# cutoff.net
KiCad netlist of a schematic drawn in EAGLE
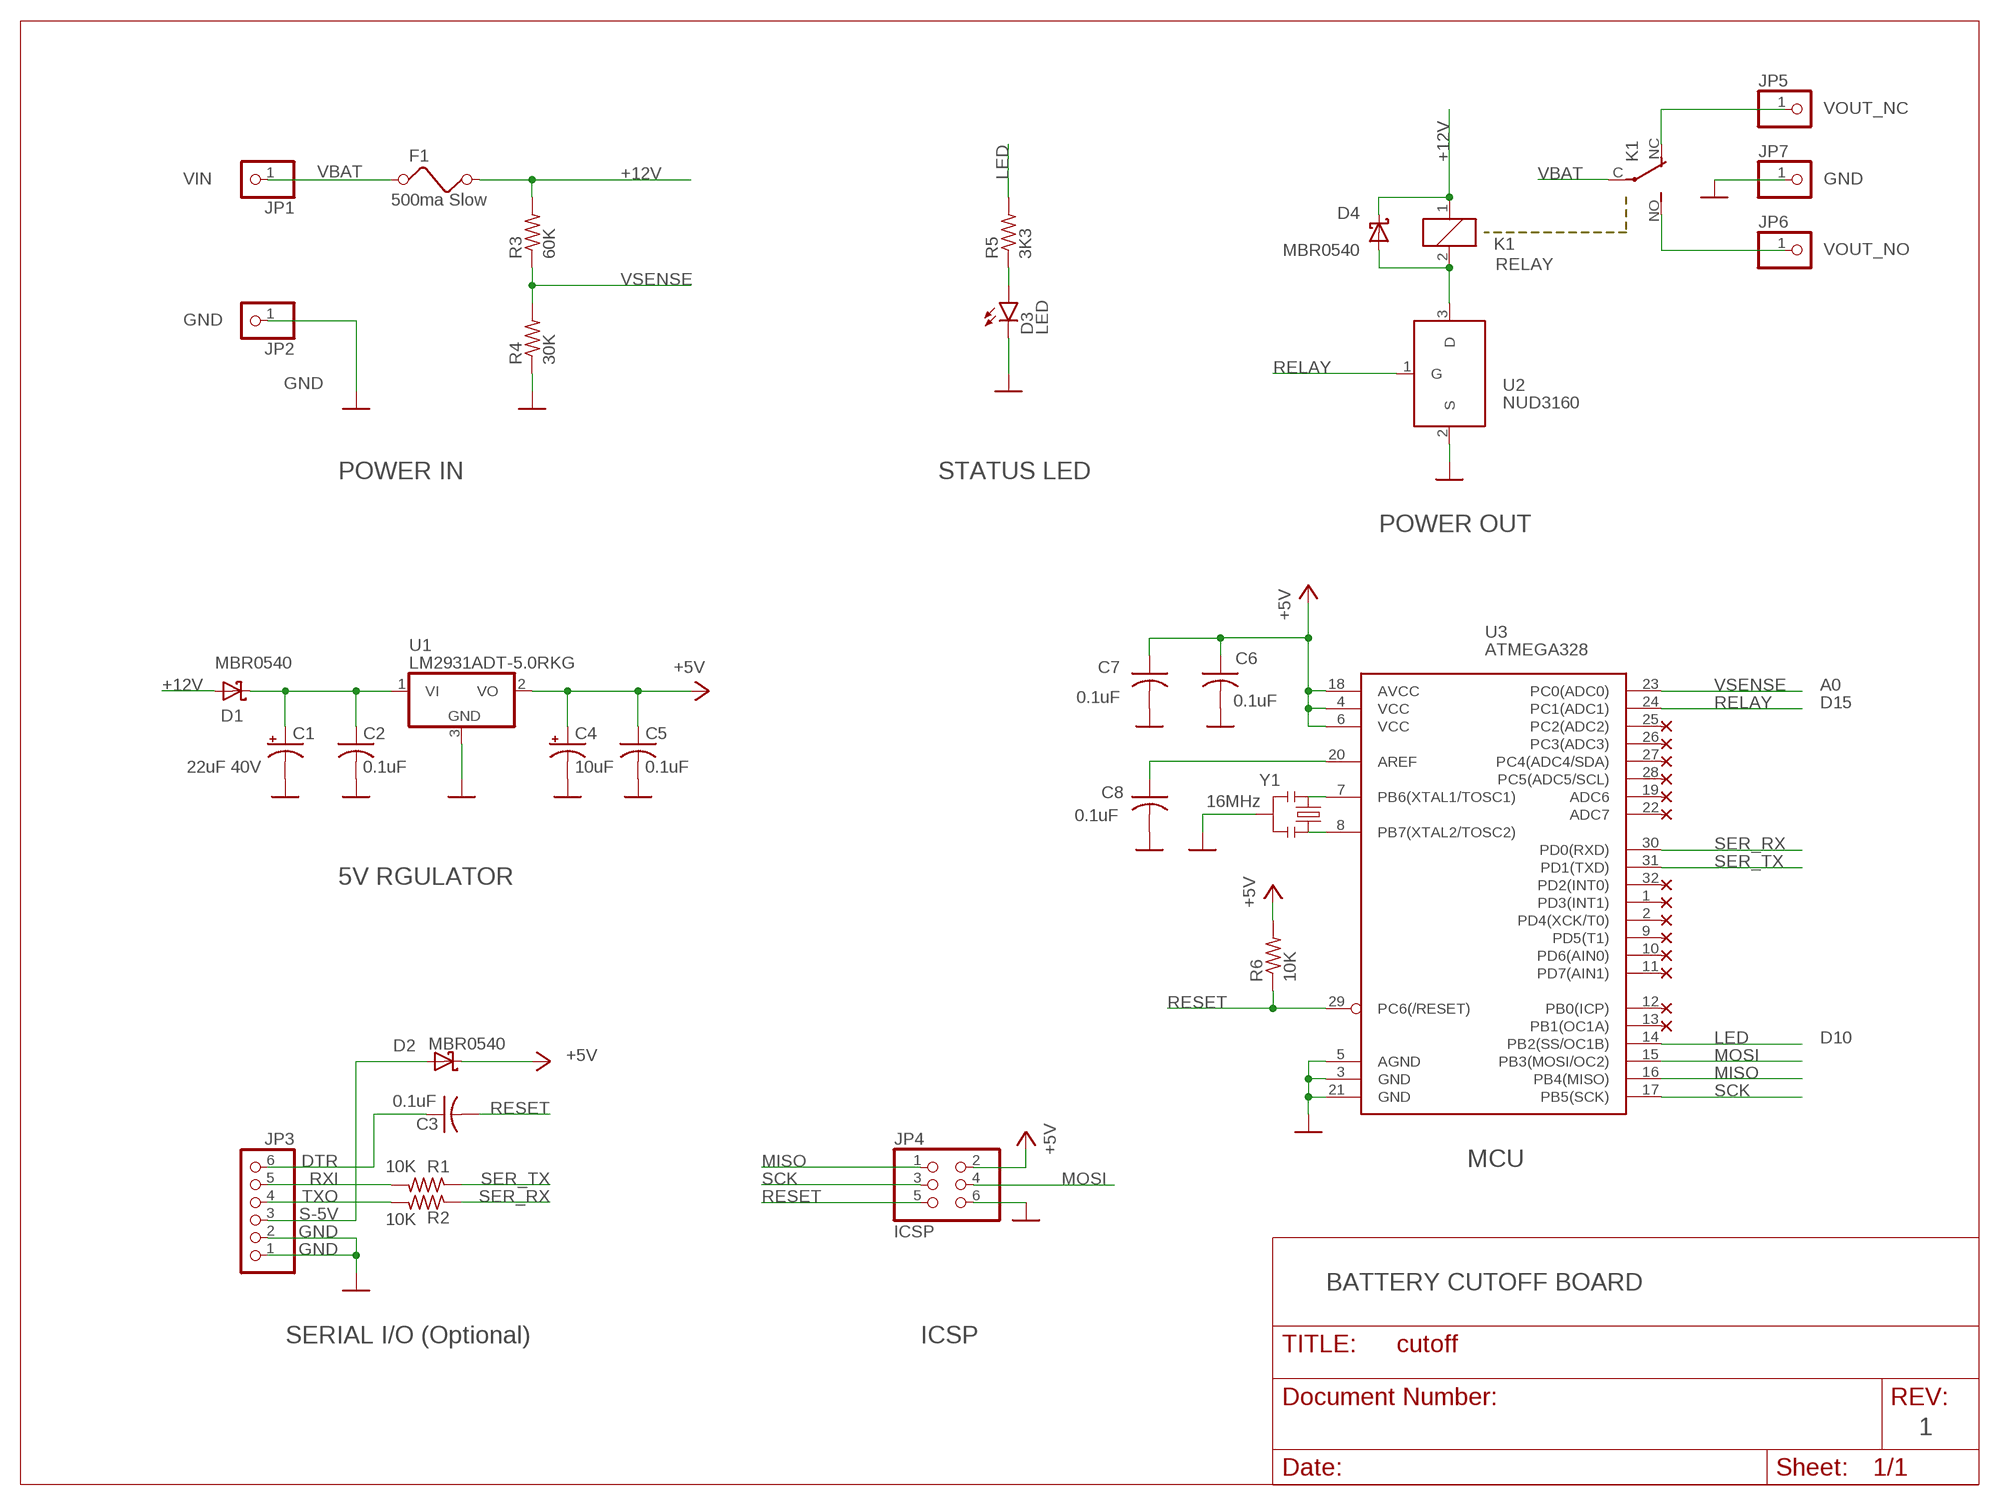
[diagram p0: schematic, sheet 1]

(export (version "E")
  (design (tool "Eeschema 10.0.6"))
  (components
    (comp (ref "C1")
      (value "22uF 40V")
      (footprint "eagle-import:UD-6,3X5,8_NICHICON")
      (libsource (lib "eagle-import") (part "CPOL-USUD-6,3X5,8"))
    )
    (comp (ref "C2")
      (value "0.1uF")
      (footprint "eagle-import:C0603K")
      (libsource (lib "eagle-import") (part "C-USC0603K"))
    )
    (comp (ref "C3")
      (value "0.1uF")
      (footprint "eagle-import:C0603K")
      (libsource (lib "eagle-import") (part "C-USC0603K"))
    )
    (comp (ref "C4")
      (value "10uF")
      (footprint "eagle-import:A_3216-18R")
      (libsource (lib "eagle-import") (part "CPOL-USA/3216-18R"))
    )
    (comp (ref "C5")
      (value "0.1uF")
      (footprint "eagle-import:C0603K")
      (libsource (lib "eagle-import") (part "C-USC0603K"))
    )
    (comp (ref "C6")
      (value "0.1uF")
      (footprint "eagle-import:C0603K")
      (libsource (lib "eagle-import") (part "C-USC0603K"))
    )
    (comp (ref "C7")
      (value "0.1uF")
      (footprint "eagle-import:C0603K")
      (libsource (lib "eagle-import") (part "C-USC0603K"))
    )
    (comp (ref "C8")
      (value "0.1uF")
      (footprint "eagle-import:C0603K")
      (libsource (lib "eagle-import") (part "C-USC0603K"))
    )
    (comp (ref "D1")
      (value "MBR0540")
      (footprint "eagle-import:SOD123FL")
      (libsource (lib "eagle-import") (part "SMF5.0AT1"))
    )
    (comp (ref "D2")
      (value "MBR0540")
      (footprint "eagle-import:SOD123FL")
      (libsource (lib "eagle-import") (part "SMF5.0AT1"))
    )
    (comp (ref "D3")
      (value "LED")
      (footprint "eagle-import:LED")
      (libsource (lib "eagle-import") (part "LED"))
    )
    (comp (ref "D4")
      (value "MBR0540")
      (footprint "eagle-import:SOD123FL")
      (libsource (lib "eagle-import") (part "SMF5.0AT1"))
    )
    (comp (ref "F1")
      (value "500ma Slow")
      (footprint "eagle-import:1206")
      (libsource (lib "eagle-import") (part "FUSE"))
    )
    (comp (ref "JP1")
      (value "WIRE_PAD")
      (footprint "eagle-import:WIRE_PAD")
      (libsource (lib "eagle-import") (part "WIRE_PAD"))
    )
    (comp (ref "JP2")
      (value "WIRE_PAD")
      (footprint "eagle-import:WIRE_PAD")
      (libsource (lib "eagle-import") (part "WIRE_PAD"))
    )
    (comp (ref "JP3")
      (value "PINHD-1X6")
      (footprint "eagle-import:1X06")
      (libsource (lib "eagle-import") (part "PINHD-1X6"))
    )
    (comp (ref "JP4")
      (value "ICSP")
      (footprint "eagle-import:2X03")
      (libsource (lib "eagle-import") (part "PINHD-2X3"))
    )
    (comp (ref "JP5")
      (value "WIRE_PAD")
      (footprint "eagle-import:WIRE_PAD")
      (libsource (lib "eagle-import") (part "WIRE_PAD"))
    )
    (comp (ref "JP6")
      (value "WIRE_PAD")
      (footprint "eagle-import:WIRE_PAD")
      (libsource (lib "eagle-import") (part "WIRE_PAD"))
    )
    (comp (ref "JP7")
      (value "WIRE_PAD")
      (footprint "eagle-import:WIRE_PAD")
      (libsource (lib "eagle-import") (part "WIRE_PAD"))
    )
    (comp (ref "K1")
      (value "RELAY")
      (footprint "eagle-import:RELAY")
      (libsource (lib "eagle-import") (part "RELAY"))
    )
    (comp (ref "R1")
      (value "10K")
      (footprint "eagle-import:R0402")
      (libsource (lib "eagle-import") (part "R-US_R0402"))
    )
    (comp (ref "R2")
      (value "10K")
      (footprint "eagle-import:R0402")
      (libsource (lib "eagle-import") (part "R-US_R0402"))
    )
    (comp (ref "R3")
      (value "60K")
      (footprint "eagle-import:R0402")
      (libsource (lib "eagle-import") (part "R-US_R0402"))
    )
    (comp (ref "R4")
      (value "30K")
      (footprint "eagle-import:R0402")
      (libsource (lib "eagle-import") (part "R-US_R0402"))
    )
    (comp (ref "R5")
      (value "3K3")
      (footprint "eagle-import:R0402")
      (libsource (lib "eagle-import") (part "R-US_R0402"))
    )
    (comp (ref "R6")
      (value "10K")
      (footprint "eagle-import:R0402")
      (libsource (lib "eagle-import") (part "R-US_R0402"))
    )
    (comp (ref "U1")
      (value "LM2931ADT-5.0RKG")
      (footprint "eagle-import:LDO")
      (libsource (lib "eagle-import") (part "LDODT"))
    )
    (comp (ref "U2")
      (value "NUD3160")
      (footprint "eagle-import:SOT23")
      (libsource (lib "eagle-import") (part "NUD3160"))
    )
    (comp (ref "U3")
      (value "ATMEGA328")
      (footprint "eagle-import:TQFP32-08")
      (libsource (lib "eagle-import") (part "ATMEGA328"))
    )
    (comp (ref "Y1")
      (value "16MHz")
      (footprint "eagle-import:RESONATOR-SMD")
      (libsource (lib "eagle-import") (part "RESONATORSMD"))
    )
  )
  (nets
    (net (code "1") (name "+5V") (class "Default")
      (node (ref "C4") (pin "+") (pinfunction "+_+") (pintype "passive"))
      (node (ref "C5") (pin "1") (pinfunction "1_1") (pintype "passive"))
      (node (ref "C6") (pin "1") (pinfunction "1_1") (pintype "passive"))
      (node (ref "C7") (pin "1") (pinfunction "1_1") (pintype "passive"))
      (node (ref "D2") (pin "C") (pinfunction "C_C") (pintype "passive"))
      (node (ref "JP4") (pin "2") (pinfunction "2_2") (pintype "passive"))
      (node (ref "R6") (pin "2") (pinfunction "2_2") (pintype "passive"))
      (node (ref "U1") (pin "2") (pinfunction "VO_2") (pintype "passive"))
      (node (ref "U3") (pin "18") (pinfunction "AVCC_18") (pintype "power_in"))
      (node (ref "U3") (pin "4") (pinfunction "VCC_4") (pintype "power_in"))
      (node (ref "U3") (pin "6") (pinfunction "VCC_6") (pintype "power_in"))
    )
    (net (code "2") (name "/+12V") (class "Default")
      (node (ref "D1") (pin "A") (pinfunction "A_A") (pintype "passive"))
      (node (ref "D4") (pin "C") (pinfunction "C_C") (pintype "passive"))
      (node (ref "F1") (pin "2") (pinfunction "2_2") (pintype "passive"))
      (node (ref "K1") (pin "1") (pinfunction "1_1") (pintype "passive"))
      (node (ref "R3") (pin "2") (pinfunction "2_2") (pintype "passive"))
    )
    (net (code "3") (name "/DTR") (class "Default")
      (node (ref "C3") (pin "1") (pinfunction "1_1") (pintype "passive"))
      (node (ref "JP3") (pin "6") (pinfunction "6_6") (pintype "passive"))
    )
    (net (code "4") (name "/LED") (class "Default")
      (node (ref "R5") (pin "2") (pinfunction "2_2") (pintype "passive"))
      (node (ref "U3") (pin "14") (pinfunction "PB2(SS/OC1B)_14") (pintype "bidirectional"))
    )
    (net (code "5") (name "/MISO") (class "Default")
      (node (ref "JP4") (pin "1") (pinfunction "1_1") (pintype "passive"))
      (node (ref "U3") (pin "16") (pinfunction "PB4(MISO)_16") (pintype "bidirectional"))
    )
    (net (code "6") (name "/MOSI") (class "Default")
      (node (ref "JP4") (pin "4") (pinfunction "4_4") (pintype "passive"))
      (node (ref "U3") (pin "15") (pinfunction "PB3(MOSI/OC2)_15") (pintype "bidirectional"))
    )
    (net (code "7") (name "/RELAY") (class "Default")
      (node (ref "U2") (pin "1") (pinfunction "G_1") (pintype "passive"))
      (node (ref "U3") (pin "24") (pinfunction "PC1(ADC1)_24") (pintype "bidirectional"))
    )
    (net (code "8") (name "/RESET") (class "Default")
      (node (ref "C3") (pin "2") (pinfunction "2_2") (pintype "passive"))
      (node (ref "JP4") (pin "5") (pinfunction "5_5") (pintype "passive"))
      (node (ref "R6") (pin "1") (pinfunction "1_1") (pintype "passive"))
      (node (ref "U3") (pin "29") (pinfunction "PC6(/RESET)_29") (pintype "bidirectional"))
    )
    (net (code "9") (name "/RXI") (class "Default")
      (node (ref "JP3") (pin "5") (pinfunction "5_5") (pintype "passive"))
      (node (ref "R1") (pin "2") (pinfunction "2_2") (pintype "passive"))
    )
    (net (code "10") (name "/S-5V") (class "Default")
      (node (ref "D2") (pin "A") (pinfunction "A_A") (pintype "passive"))
      (node (ref "JP3") (pin "3") (pinfunction "3_3") (pintype "passive"))
    )
    (net (code "11") (name "/SCK") (class "Default")
      (node (ref "JP4") (pin "3") (pinfunction "3_3") (pintype "passive"))
      (node (ref "U3") (pin "17") (pinfunction "PB5(SCK)_17") (pintype "bidirectional"))
    )
    (net (code "12") (name "/SER_RX") (class "Default")
      (node (ref "R2") (pin "1") (pinfunction "1_1") (pintype "passive"))
      (node (ref "U3") (pin "30") (pinfunction "PD0(RXD)_30") (pintype "bidirectional"))
    )
    (net (code "13") (name "/SER_TX") (class "Default")
      (node (ref "R1") (pin "1") (pinfunction "1_1") (pintype "passive"))
      (node (ref "U3") (pin "31") (pinfunction "PD1(TXD)_31") (pintype "bidirectional"))
    )
    (net (code "14") (name "/TXO") (class "Default")
      (node (ref "JP3") (pin "4") (pinfunction "4_4") (pintype "passive"))
      (node (ref "R2") (pin "2") (pinfunction "2_2") (pintype "passive"))
    )
    (net (code "15") (name "/VBAT") (class "Default")
      (node (ref "F1") (pin "1") (pinfunction "1_1") (pintype "passive"))
      (node (ref "JP1") (pin "1") (pinfunction "1_1") (pintype "passive"))
      (node (ref "K1") (pin "C") (pinfunction "P_C") (pintype "passive"))
    )
    (net (code "16") (name "/VSENSE") (class "Default")
      (node (ref "R3") (pin "1") (pinfunction "1_1") (pintype "passive"))
      (node (ref "R4") (pin "2") (pinfunction "2_2") (pintype "passive"))
      (node (ref "U3") (pin "23") (pinfunction "PC0(ADC0)_23") (pintype "bidirectional"))
    )
    (net (code "17") (name "GND") (class "Default")
      (node (ref "C1") (pin "-") (pinfunction "-_-") (pintype "passive"))
      (node (ref "C2") (pin "2") (pinfunction "2_2") (pintype "passive"))
      (node (ref "C4") (pin "-") (pinfunction "-_-") (pintype "passive"))
      (node (ref "C5") (pin "2") (pinfunction "2_2") (pintype "passive"))
      (node (ref "C6") (pin "2") (pinfunction "2_2") (pintype "passive"))
      (node (ref "C7") (pin "2") (pinfunction "2_2") (pintype "passive"))
      (node (ref "C8") (pin "2") (pinfunction "2_2") (pintype "passive"))
      (node (ref "D3") (pin "K") (pinfunction "C_K") (pintype "passive"))
      (node (ref "JP2") (pin "1") (pinfunction "1_1") (pintype "passive"))
      (node (ref "JP3") (pin "1") (pinfunction "1_1") (pintype "passive"))
      (node (ref "JP3") (pin "2") (pinfunction "2_2") (pintype "passive"))
      (node (ref "JP4") (pin "6") (pinfunction "6_6") (pintype "passive"))
      (node (ref "JP7") (pin "1") (pinfunction "1_1") (pintype "passive"))
      (node (ref "R4") (pin "1") (pinfunction "1_1") (pintype "passive"))
      (node (ref "U1") (pin "3") (pinfunction "GND_3") (pintype "passive"))
      (node (ref "U2") (pin "2") (pinfunction "S_2") (pintype "passive"))
      (node (ref "U3") (pin "21") (pinfunction "GND_21") (pintype "power_in"))
      (node (ref "U3") (pin "3") (pinfunction "GND_3") (pintype "power_in"))
      (node (ref "U3") (pin "5") (pinfunction "AGND_5") (pintype "power_in"))
      (node (ref "Y1") (pin "2") (pinfunction "2_2") (pintype "passive"))
    )
    (net (code "18") (name "Net-(D3-PadA)") (class "Default")
      (node (ref "D3") (pin "A") (pinfunction "A_A") (pintype "passive"))
      (node (ref "R5") (pin "1") (pinfunction "1_1") (pintype "passive"))
    )
    (net (code "19") (name "Net-(K1B-O)") (class "Default")
      (node (ref "JP5") (pin "1") (pinfunction "1_1") (pintype "passive"))
      (node (ref "K1") (pin "NC") (pinfunction "O_NC") (pintype "passive"))
    )
    (net (code "20") (name "Net-(K1B-S)") (class "Default")
      (node (ref "JP6") (pin "1") (pinfunction "1_1") (pintype "passive"))
      (node (ref "K1") (pin "NO") (pinfunction "S_NO") (pintype "passive"))
    )
    (net (code "21") (name "Net-(U1-VI)") (class "Default")
      (node (ref "C1") (pin "+") (pinfunction "+_+") (pintype "passive"))
      (node (ref "C2") (pin "1") (pinfunction "1_1") (pintype "passive"))
      (node (ref "D1") (pin "C") (pinfunction "C_C") (pintype "passive"))
      (node (ref "U1") (pin "1") (pinfunction "VI_1") (pintype "input"))
    )
    (net (code "22") (name "Net-(U2-D)") (class "Default")
      (node (ref "D4") (pin "A") (pinfunction "A_A") (pintype "passive"))
      (node (ref "K1") (pin "2") (pinfunction "2_2") (pintype "passive"))
      (node (ref "U2") (pin "3") (pinfunction "D_3") (pintype "passive"))
    )
    (net (code "23") (name "Net-(U3-AREF)") (class "Default")
      (node (ref "C8") (pin "1") (pinfunction "1_1") (pintype "passive"))
      (node (ref "U3") (pin "20") (pinfunction "AREF_20") (pintype "power_in"))
    )
    (net (code "24") (name "Net-(U3-PB6(XTAL1{slash}TOSC1))") (class "Default")
      (node (ref "U3") (pin "7") (pinfunction "PB6(XTAL1/TOSC1)_7") (pintype "bidirectional"))
      (node (ref "Y1") (pin "3") (pinfunction "3_3") (pintype "passive"))
    )
    (net (code "25") (name "Net-(U3-PB7(XTAL2{slash}TOSC2))") (class "Default")
      (node (ref "U3") (pin "8") (pinfunction "PB7(XTAL2/TOSC2)_8") (pintype "bidirectional"))
      (node (ref "Y1") (pin "1") (pinfunction "1_1") (pintype "passive"))
    )
    (net (code "26") (name "unconnected-(U3-ADC6-Pad19)") (class "Default")
      (node (ref "U3") (pin "19") (pinfunction "ADC6_19") (pintype "bidirectional"))
    )
    (net (code "27") (name "unconnected-(U3-ADC7-Pad22)") (class "Default")
      (node (ref "U3") (pin "22") (pinfunction "ADC7_22") (pintype "bidirectional"))
    )
    (net (code "28") (name "unconnected-(U3-PB0(ICP)-Pad12)") (class "Default")
      (node (ref "U3") (pin "12") (pinfunction "PB0(ICP)_12") (pintype "bidirectional"))
    )
    (net (code "29") (name "unconnected-(U3-PB1(OC1A)-Pad13)") (class "Default")
      (node (ref "U3") (pin "13") (pinfunction "PB1(OC1A)_13") (pintype "bidirectional"))
    )
    (net (code "30") (name "unconnected-(U3-PC2(ADC2)-Pad25)") (class "Default")
      (node (ref "U3") (pin "25") (pinfunction "PC2(ADC2)_25") (pintype "bidirectional"))
    )
    (net (code "31") (name "unconnected-(U3-PC3(ADC3)-Pad26)") (class "Default")
      (node (ref "U3") (pin "26") (pinfunction "PC3(ADC3)_26") (pintype "bidirectional"))
    )
    (net (code "32") (name "unconnected-(U3-PC4(ADC4{slash}SDA)-Pad27)") (class "Default")
      (node (ref "U3") (pin "27") (pinfunction "PC4(ADC4/SDA)_27") (pintype "bidirectional"))
    )
    (net (code "33") (name "unconnected-(U3-PC5(ADC5{slash}SCL)-Pad28)") (class "Default")
      (node (ref "U3") (pin "28") (pinfunction "PC5(ADC5/SCL)_28") (pintype "bidirectional"))
    )
    (net (code "34") (name "unconnected-(U3-PD2(INT0)-Pad32)") (class "Default")
      (node (ref "U3") (pin "32") (pinfunction "PD2(INT0)_32") (pintype "bidirectional"))
    )
    (net (code "35") (name "unconnected-(U3-PD3(INT1)-Pad1)") (class "Default")
      (node (ref "U3") (pin "1") (pinfunction "PD3(INT1)_1") (pintype "bidirectional"))
    )
    (net (code "36") (name "unconnected-(U3-PD4(XCK{slash}T0)-Pad2)") (class "Default")
      (node (ref "U3") (pin "2") (pinfunction "PD4(XCK/T0)_2") (pintype "bidirectional"))
    )
    (net (code "37") (name "unconnected-(U3-PD5(T1)-Pad9)") (class "Default")
      (node (ref "U3") (pin "9") (pinfunction "PD5(T1)_9") (pintype "bidirectional"))
    )
    (net (code "38") (name "unconnected-(U3-PD6(AIN0)-Pad10)") (class "Default")
      (node (ref "U3") (pin "10") (pinfunction "PD6(AIN0)_10") (pintype "bidirectional"))
    )
    (net (code "39") (name "unconnected-(U3-PD7(AIN1)-Pad11)") (class "Default")
      (node (ref "U3") (pin "11") (pinfunction "PD7(AIN1)_11") (pintype "bidirectional"))
    )
  )
)
